# final.net
KiCad netlist of a schematic drawn in EAGLE
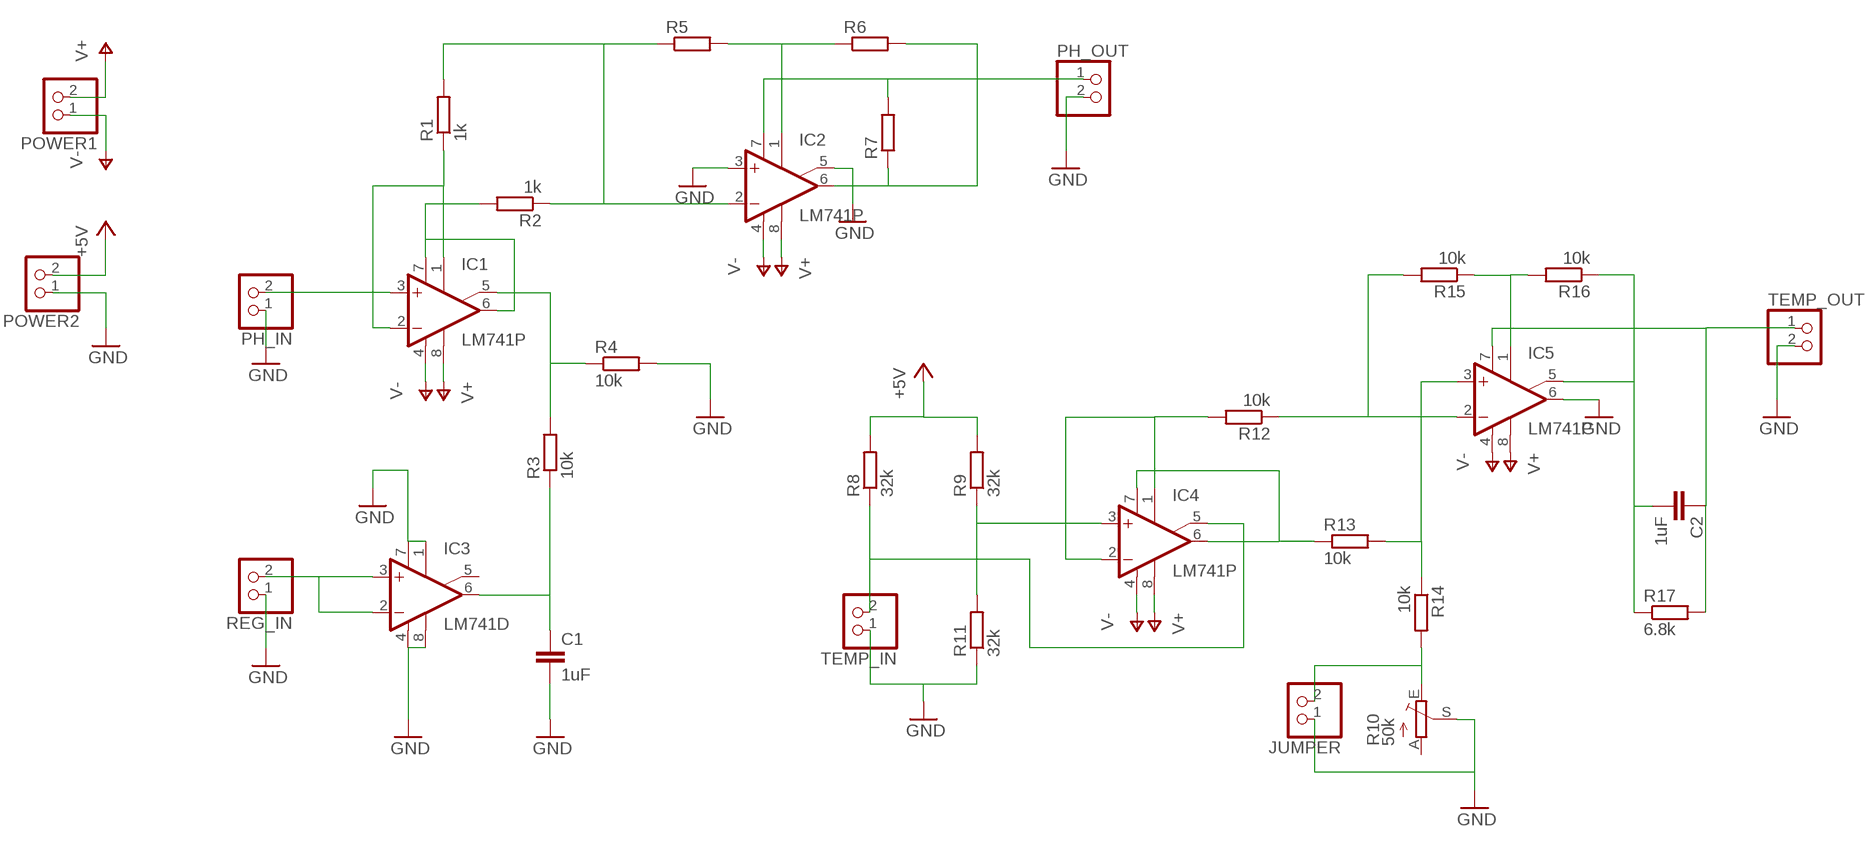
[diagram p0: schematic, sheet 1]

(export (version "E")
  (design (tool "Eeschema 10.0.6"))
  (components
    (comp (ref "C1")
      (value "1uF")
      (footprint "eagle-import:C0805K")
      (libsource (lib "eagle-import") (part "C-EUC0805K"))
    )
    (comp (ref "C2")
      (value "1uF")
      (footprint "eagle-import:C0805K")
      (libsource (lib "eagle-import") (part "C-EUC0805K"))
    )
    (comp (ref "IC1")
      (value "LM741P")
      (footprint "eagle-import:DIL08")
      (libsource (lib "eagle-import") (part "741PLM"))
    )
    (comp (ref "IC2")
      (value "LM741P")
      (footprint "eagle-import:DIL08")
      (libsource (lib "eagle-import") (part "741PLM"))
    )
    (comp (ref "IC3")
      (value "LM741D")
      (footprint "eagle-import:SO08")
      (libsource (lib "eagle-import") (part "741DLM"))
    )
    (comp (ref "IC4")
      (value "LM741P")
      (footprint "eagle-import:DIL08")
      (libsource (lib "eagle-import") (part "741PLM"))
    )
    (comp (ref "IC5")
      (value "LM741P")
      (footprint "eagle-import:DIL08")
      (libsource (lib "eagle-import") (part "741PLM"))
    )
    (comp (ref "JUMPER")
      (value "PINHD-1X2")
      (footprint "eagle-import:1X02")
      (libsource (lib "eagle-import") (part "PINHD-1X2"))
    )
    (comp (ref "PH_IN")
      (value "PINHD-1X2")
      (footprint "eagle-import:1X02")
      (libsource (lib "eagle-import") (part "PINHD-1X2"))
    )
    (comp (ref "PH_OUT")
      (value "PINHD-1X2")
      (footprint "eagle-import:1X02")
      (libsource (lib "eagle-import") (part "PINHD-1X2"))
    )
    (comp (ref "POWER1")
      (value "PINHD-1X2")
      (footprint "eagle-import:1X02")
      (libsource (lib "eagle-import") (part "PINHD-1X2"))
    )
    (comp (ref "POWER2")
      (value "PINHD-1X2")
      (footprint "eagle-import:1X02")
      (libsource (lib "eagle-import") (part "PINHD-1X2"))
    )
    (comp (ref "R1")
      (value "1k")
      (footprint "eagle-import:R0805")
      (libsource (lib "eagle-import") (part "R-EU_R0805"))
    )
    (comp (ref "R2")
      (value "1k")
      (footprint "eagle-import:R0805")
      (libsource (lib "eagle-import") (part "R-EU_R0805"))
    )
    (comp (ref "R3")
      (value "10k")
      (footprint "eagle-import:R0805")
      (libsource (lib "eagle-import") (part "R-EU_R0805"))
    )
    (comp (ref "R4")
      (value "10k")
      (footprint "eagle-import:R0805")
      (libsource (lib "eagle-import") (part "R-EU_R0805"))
    )
    (comp (ref "R5")
      (value "R-EU_R0805")
      (footprint "eagle-import:R0805")
      (libsource (lib "eagle-import") (part "R-EU_R0805"))
    )
    (comp (ref "R6")
      (value "R-EU_R0805")
      (footprint "eagle-import:R0805")
      (libsource (lib "eagle-import") (part "R-EU_R0805"))
    )
    (comp (ref "R7")
      (value "R-EU_R0805")
      (footprint "eagle-import:R0805")
      (libsource (lib "eagle-import") (part "R-EU_R0805"))
    )
    (comp (ref "R8")
      (value "32k")
      (footprint "eagle-import:R0805")
      (libsource (lib "eagle-import") (part "R-EU_R0805"))
    )
    (comp (ref "R9")
      (value "32k")
      (footprint "eagle-import:R0805")
      (libsource (lib "eagle-import") (part "R-EU_R0805"))
    )
    (comp (ref "R10")
      (value "50k")
      (footprint "eagle-import:S64W")
      (libsource (lib "eagle-import") (part "TRIM_EU-S64W"))
    )
    (comp (ref "R11")
      (value "32k")
      (footprint "eagle-import:R0805")
      (libsource (lib "eagle-import") (part "R-EU_R0805"))
    )
    (comp (ref "R12")
      (value "10k")
      (footprint "eagle-import:R0805")
      (libsource (lib "eagle-import") (part "R-EU_R0805"))
    )
    (comp (ref "R13")
      (value "10k")
      (footprint "eagle-import:R0805")
      (libsource (lib "eagle-import") (part "R-EU_R0805"))
    )
    (comp (ref "R14")
      (value "10k")
      (footprint "eagle-import:R0805")
      (libsource (lib "eagle-import") (part "R-EU_R0805"))
    )
    (comp (ref "R15")
      (value "10k")
      (footprint "eagle-import:R0805")
      (libsource (lib "eagle-import") (part "R-EU_R0805"))
    )
    (comp (ref "R16")
      (value "10k")
      (footprint "eagle-import:R0805")
      (libsource (lib "eagle-import") (part "R-EU_R0805"))
    )
    (comp (ref "R17")
      (value "6.8k")
      (footprint "eagle-import:R0805")
      (libsource (lib "eagle-import") (part "R-EU_R0805"))
    )
    (comp (ref "REG_IN")
      (value "PINHD-1X2")
      (footprint "eagle-import:1X02")
      (libsource (lib "eagle-import") (part "PINHD-1X2"))
    )
    (comp (ref "TEMP_IN")
      (value "PINHD-1X2")
      (footprint "eagle-import:1X02")
      (libsource (lib "eagle-import") (part "PINHD-1X2"))
    )
    (comp (ref "TEMP_OUT")
      (value "PINHD-1X2")
      (footprint "eagle-import:1X02")
      (libsource (lib "eagle-import") (part "PINHD-1X2"))
    )
  )
  (nets
    (net (code "1") (name "+5V") (class "Default")
      (node (ref "POWER2") (pin "2") (pinfunction "2_2") (pintype "passive"))
      (node (ref "R8") (pin "2") (pinfunction "2_2") (pintype "passive"))
      (node (ref "R9") (pin "2") (pinfunction "2_2") (pintype "passive"))
    )
    (net (code "2") (name "GND") (class "Default")
      (node (ref "C1") (pin "2") (pinfunction "2_2") (pintype "passive"))
      (node (ref "IC2") (pin "3") (pinfunction "+IN_3") (pintype "input"))
      (node (ref "IC2") (pin "5") (pinfunction "ON2_5") (pintype "passive"))
      (node (ref "IC3") (pin "1") (pinfunction "ON1_1") (pintype "passive"))
      (node (ref "IC3") (pin "4") (pinfunction "V-_4") (pintype "power_in"))
      (node (ref "IC3") (pin "7") (pinfunction "V+_7") (pintype "power_in"))
      (node (ref "IC3") (pin "8") (pinfunction "OPT_8") (pintype "passive"))
      (node (ref "IC5") (pin "6") (pinfunction "OUT_6") (pintype "output"))
      (node (ref "JUMPER") (pin "1") (pinfunction "1_1") (pintype "passive"))
      (node (ref "PH_IN") (pin "1") (pinfunction "1_1") (pintype "passive"))
      (node (ref "PH_OUT") (pin "2") (pinfunction "2_2") (pintype "passive"))
      (node (ref "POWER2") (pin "1") (pinfunction "1_1") (pintype "passive"))
      (node (ref "R10") (pin "S") (pinfunction "S_S") (pintype "passive"))
      (node (ref "R11") (pin "1") (pinfunction "1_1") (pintype "passive"))
      (node (ref "R4") (pin "2") (pinfunction "2_2") (pintype "passive"))
      (node (ref "REG_IN") (pin "1") (pinfunction "1_1") (pintype "passive"))
      (node (ref "TEMP_IN") (pin "1") (pinfunction "1_1") (pintype "passive"))
      (node (ref "TEMP_OUT") (pin "2") (pinfunction "2_2") (pintype "passive"))
    )
    (net (code "3") (name "Net-(IC1-+IN)") (class "Default")
      (node (ref "IC1") (pin "3") (pinfunction "+IN_3") (pintype "input"))
      (node (ref "PH_IN") (pin "2") (pinfunction "2_2") (pintype "passive"))
    )
    (net (code "4") (name "Net-(IC1--IN)") (class "Default")
      (node (ref "IC1") (pin "1") (pinfunction "ON1_1") (pintype "passive"))
      (node (ref "IC1") (pin "2") (pinfunction "-IN_2") (pintype "input"))
      (node (ref "R1") (pin "1") (pinfunction "1_1") (pintype "passive"))
    )
    (net (code "5") (name "Net-(IC1-ON2)") (class "Default")
      (node (ref "IC1") (pin "5") (pinfunction "ON2_5") (pintype "passive"))
      (node (ref "R3") (pin "2") (pinfunction "2_2") (pintype "passive"))
      (node (ref "R4") (pin "1") (pinfunction "1_1") (pintype "passive"))
    )
    (net (code "6") (name "Net-(IC1-OUT)") (class "Default")
      (node (ref "IC1") (pin "6") (pinfunction "OUT_6") (pintype "output"))
      (node (ref "IC1") (pin "7") (pinfunction "V+_7") (pintype "power_in"))
      (node (ref "R2") (pin "2") (pinfunction "2_2") (pintype "passive"))
    )
    (net (code "7") (name "Net-(IC2--IN)") (class "Default")
      (node (ref "IC2") (pin "2") (pinfunction "-IN_2") (pintype "input"))
      (node (ref "R1") (pin "2") (pinfunction "2_2") (pintype "passive"))
      (node (ref "R2") (pin "1") (pinfunction "1_1") (pintype "passive"))
      (node (ref "R5") (pin "1") (pinfunction "1_1") (pintype "passive"))
    )
    (net (code "8") (name "Net-(IC2-ON1)") (class "Default")
      (node (ref "IC2") (pin "1") (pinfunction "ON1_1") (pintype "passive"))
      (node (ref "R5") (pin "2") (pinfunction "2_2") (pintype "passive"))
      (node (ref "R6") (pin "1") (pinfunction "1_1") (pintype "passive"))
    )
    (net (code "9") (name "Net-(IC2-OUT)") (class "Default")
      (node (ref "IC2") (pin "6") (pinfunction "OUT_6") (pintype "output"))
      (node (ref "R6") (pin "2") (pinfunction "2_2") (pintype "passive"))
      (node (ref "R7") (pin "1") (pinfunction "1_1") (pintype "passive"))
    )
    (net (code "10") (name "Net-(IC2-V+)") (class "Default")
      (node (ref "IC2") (pin "7") (pinfunction "V+_7") (pintype "power_in"))
      (node (ref "PH_OUT") (pin "1") (pinfunction "1_1") (pintype "passive"))
      (node (ref "R7") (pin "2") (pinfunction "2_2") (pintype "passive"))
    )
    (net (code "11") (name "Net-(IC3-+IN)") (class "Default")
      (node (ref "IC3") (pin "2") (pinfunction "-IN_2") (pintype "input"))
      (node (ref "IC3") (pin "3") (pinfunction "+IN_3") (pintype "input"))
      (node (ref "REG_IN") (pin "2") (pinfunction "2_2") (pintype "passive"))
    )
    (net (code "12") (name "Net-(IC3-OUT)") (class "Default")
      (node (ref "C1") (pin "1") (pinfunction "1_1") (pintype "passive"))
      (node (ref "IC3") (pin "6") (pinfunction "OUT_6") (pintype "output"))
      (node (ref "R3") (pin "1") (pinfunction "1_1") (pintype "passive"))
    )
    (net (code "13") (name "Net-(IC4-+IN)") (class "Default")
      (node (ref "IC4") (pin "3") (pinfunction "+IN_3") (pintype "input"))
      (node (ref "R11") (pin "2") (pinfunction "2_2") (pintype "passive"))
      (node (ref "R9") (pin "1") (pinfunction "1_1") (pintype "passive"))
    )
    (net (code "14") (name "Net-(IC4--IN)") (class "Default")
      (node (ref "IC4") (pin "1") (pinfunction "ON1_1") (pintype "passive"))
      (node (ref "IC4") (pin "2") (pinfunction "-IN_2") (pintype "input"))
      (node (ref "R12") (pin "2") (pinfunction "2_2") (pintype "passive"))
    )
    (net (code "15") (name "Net-(IC4-ON2)") (class "Default")
      (node (ref "IC4") (pin "5") (pinfunction "ON2_5") (pintype "passive"))
      (node (ref "R8") (pin "1") (pinfunction "1_1") (pintype "passive"))
      (node (ref "TEMP_IN") (pin "2") (pinfunction "2_2") (pintype "passive"))
    )
    (net (code "16") (name "Net-(IC4-OUT)") (class "Default")
      (node (ref "IC4") (pin "6") (pinfunction "OUT_6") (pintype "output"))
      (node (ref "IC4") (pin "7") (pinfunction "V+_7") (pintype "power_in"))
      (node (ref "R13") (pin "1") (pinfunction "1_1") (pintype "passive"))
    )
    (net (code "17") (name "Net-(IC5-+IN)") (class "Default")
      (node (ref "IC5") (pin "3") (pinfunction "+IN_3") (pintype "input"))
      (node (ref "R13") (pin "2") (pinfunction "2_2") (pintype "passive"))
      (node (ref "R14") (pin "1") (pinfunction "1_1") (pintype "passive"))
    )
    (net (code "18") (name "Net-(IC5--IN)") (class "Default")
      (node (ref "IC5") (pin "2") (pinfunction "-IN_2") (pintype "input"))
      (node (ref "R12") (pin "1") (pinfunction "1_1") (pintype "passive"))
      (node (ref "R15") (pin "2") (pinfunction "2_2") (pintype "passive"))
    )
    (net (code "19") (name "Net-(IC5-ON1)") (class "Default")
      (node (ref "IC5") (pin "1") (pinfunction "ON1_1") (pintype "passive"))
      (node (ref "R15") (pin "1") (pinfunction "1_1") (pintype "passive"))
      (node (ref "R16") (pin "2") (pinfunction "2_2") (pintype "passive"))
    )
    (net (code "20") (name "Net-(IC5-ON2)") (class "Default")
      (node (ref "C2") (pin "2") (pinfunction "2_2") (pintype "passive"))
      (node (ref "IC5") (pin "5") (pinfunction "ON2_5") (pintype "passive"))
      (node (ref "R16") (pin "1") (pinfunction "1_1") (pintype "passive"))
      (node (ref "R17") (pin "1") (pinfunction "1_1") (pintype "passive"))
    )
    (net (code "21") (name "Net-(IC5-V+)") (class "Default")
      (node (ref "C2") (pin "1") (pinfunction "1_1") (pintype "passive"))
      (node (ref "IC5") (pin "7") (pinfunction "V+_7") (pintype "power_in"))
      (node (ref "R17") (pin "2") (pinfunction "2_2") (pintype "passive"))
      (node (ref "TEMP_OUT") (pin "1") (pinfunction "1_1") (pintype "passive"))
    )
    (net (code "22") (name "Net-(JUMPER-Pad2)") (class "Default")
      (node (ref "JUMPER") (pin "2") (pinfunction "2_2") (pintype "passive"))
      (node (ref "R10") (pin "E") (pinfunction "E_E") (pintype "passive"))
      (node (ref "R14") (pin "2") (pinfunction "2_2") (pintype "passive"))
    )
    (net (code "23") (name "V+") (class "Default")
      (node (ref "IC1") (pin "8") (pinfunction "OPT_8") (pintype "passive"))
      (node (ref "IC2") (pin "8") (pinfunction "OPT_8") (pintype "passive"))
      (node (ref "IC4") (pin "8") (pinfunction "OPT_8") (pintype "passive"))
      (node (ref "IC5") (pin "8") (pinfunction "OPT_8") (pintype "passive"))
      (node (ref "POWER1") (pin "2") (pinfunction "2_2") (pintype "passive"))
    )
    (net (code "24") (name "V-") (class "Default")
      (node (ref "IC1") (pin "4") (pinfunction "V-_4") (pintype "power_in"))
      (node (ref "IC2") (pin "4") (pinfunction "V-_4") (pintype "power_in"))
      (node (ref "IC4") (pin "4") (pinfunction "V-_4") (pintype "power_in"))
      (node (ref "IC5") (pin "4") (pinfunction "V-_4") (pintype "power_in"))
      (node (ref "POWER1") (pin "1") (pinfunction "1_1") (pintype "passive"))
    )
    (net (code "25") (name "unconnected-(IC3-ON2-Pad5)") (class "Default")
      (node (ref "IC3") (pin "5") (pinfunction "ON2_5") (pintype "passive"))
    )
    (net (code "26") (name "unconnected-(R10-PadA)") (class "Default")
      (node (ref "R10") (pin "A") (pinfunction "A_A") (pintype "passive"))
    )
  )
)
